# main.net
KiCad netlist of a schematic drawn in Altium Designer
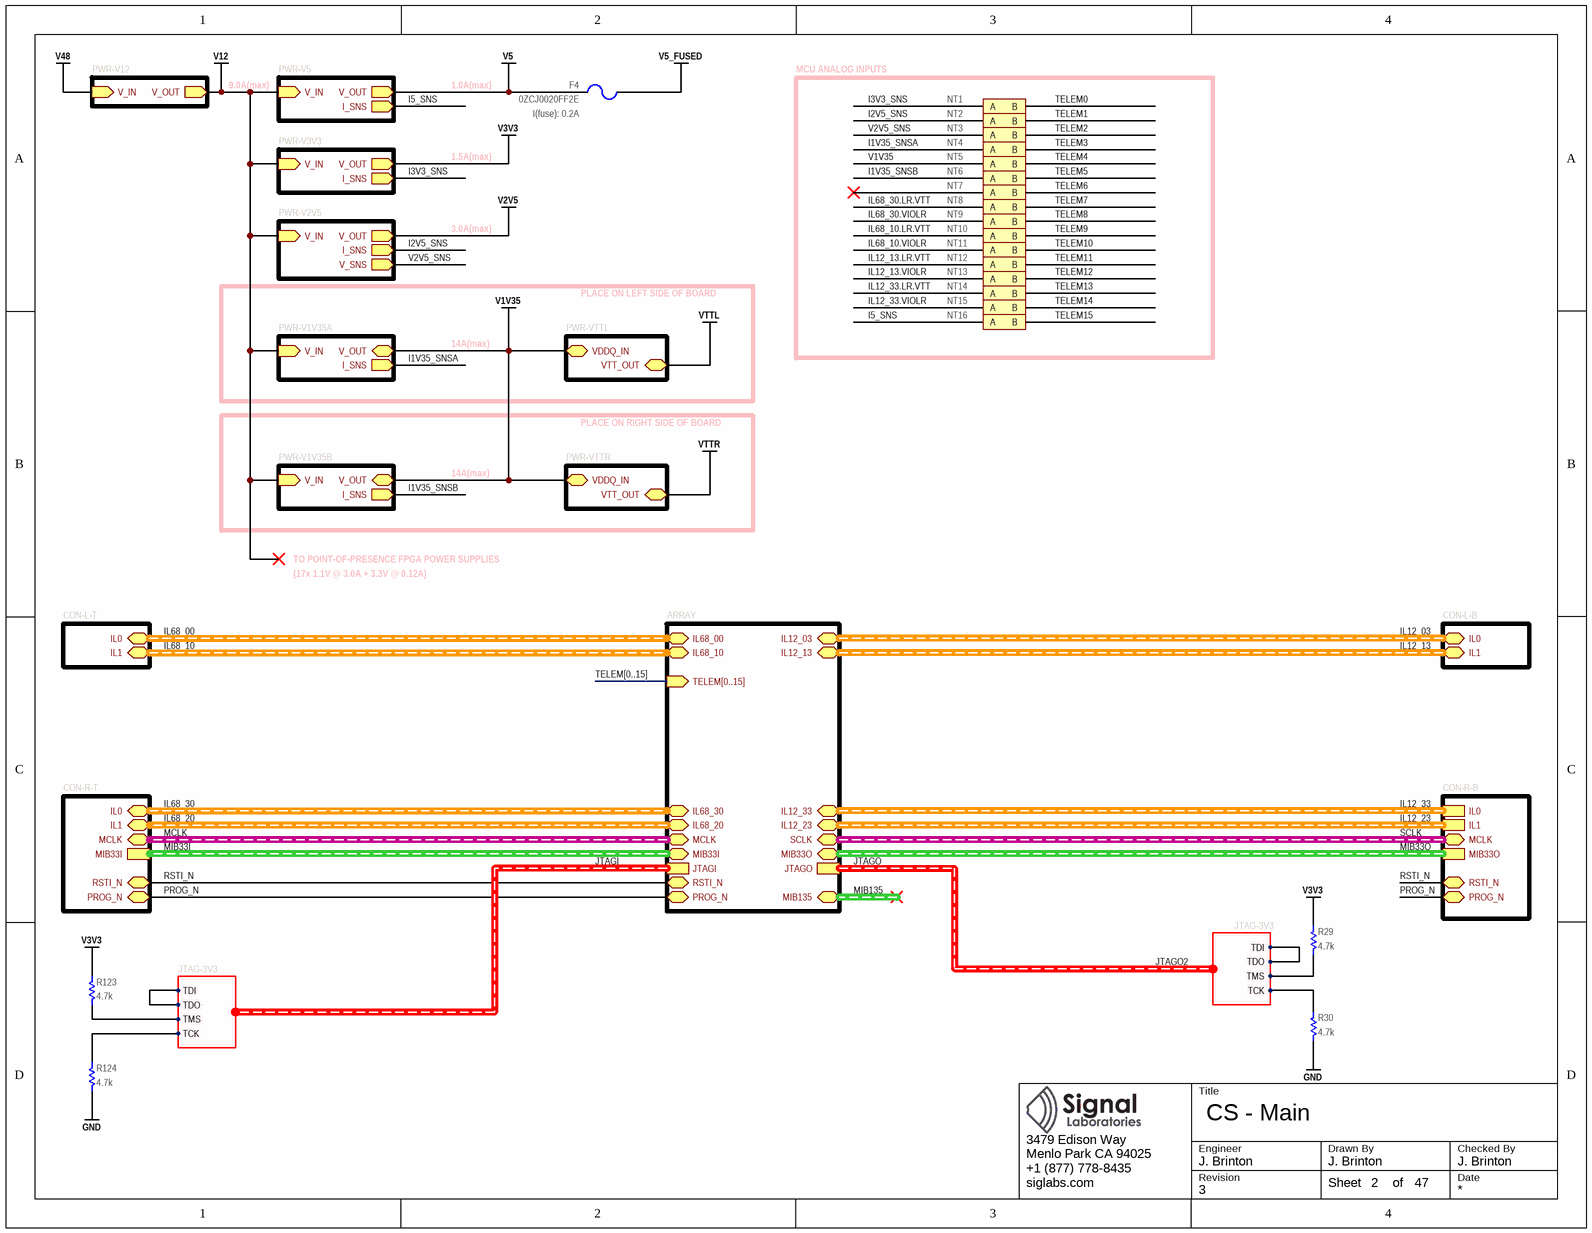
[diagram p0: main.SchDoc]

(export (version "E")
  (design (tool "Eeschema 10.0.6"))
  (components
    (comp (ref "F4")
      (value "0ZCJ0020FF2E")
      (footprint "generic:1206")
      (description "PTC Resettable Fuse, 0.2A, 30V, SMD 1206")
      (fields (field (name "MANUFACTURER") "Bell Fuse") (field (name "I(FUSE)") "0.2A"))
      (libsource (lib "bel-fuse") (part "0ZCJ0020FF2E"))
    )
    (comp (ref "NT1")
      (value "NET_TIE")
      (footprint "NET_TIE")
      (libsource (lib "copper_suicide") (part "NET_TIE"))
    )
    (comp (ref "NT2")
      (value "NET_TIE")
      (footprint "NET_TIE")
      (libsource (lib "copper_suicide") (part "NET_TIE"))
    )
    (comp (ref "NT3")
      (value "NET_TIE")
      (footprint "NET_TIE")
      (libsource (lib "copper_suicide") (part "NET_TIE"))
    )
    (comp (ref "NT4")
      (value "NET_TIE")
      (footprint "NET_TIE")
      (libsource (lib "copper_suicide") (part "NET_TIE"))
    )
    (comp (ref "NT5")
      (value "NET_TIE")
      (footprint "NET_TIE")
      (libsource (lib "copper_suicide") (part "NET_TIE"))
    )
    (comp (ref "NT6")
      (value "NET_TIE")
      (footprint "NET_TIE")
      (libsource (lib "copper_suicide") (part "NET_TIE"))
    )
    (comp (ref "NT7")
      (value "NET_TIE")
      (footprint "NET_TIE")
      (libsource (lib "copper_suicide") (part "NET_TIE"))
    )
    (comp (ref "NT8")
      (value "NET_TIE")
      (footprint "NET_TIE")
      (libsource (lib "copper_suicide") (part "NET_TIE"))
    )
    (comp (ref "NT9")
      (value "NET_TIE")
      (footprint "NET_TIE")
      (libsource (lib "copper_suicide") (part "NET_TIE"))
    )
    (comp (ref "NT10")
      (value "NET_TIE")
      (footprint "NET_TIE")
      (libsource (lib "copper_suicide") (part "NET_TIE"))
    )
    (comp (ref "NT11")
      (value "NET_TIE")
      (footprint "NET_TIE")
      (libsource (lib "copper_suicide") (part "NET_TIE"))
    )
    (comp (ref "NT12")
      (value "NET_TIE")
      (footprint "NET_TIE")
      (libsource (lib "copper_suicide") (part "NET_TIE"))
    )
    (comp (ref "NT13")
      (value "NET_TIE")
      (footprint "NET_TIE")
      (libsource (lib "copper_suicide") (part "NET_TIE"))
    )
    (comp (ref "NT14")
      (value "NET_TIE")
      (footprint "NET_TIE")
      (libsource (lib "copper_suicide") (part "NET_TIE"))
    )
    (comp (ref "NT15")
      (value "NET_TIE")
      (footprint "NET_TIE")
      (libsource (lib "copper_suicide") (part "NET_TIE"))
    )
    (comp (ref "NT16")
      (value "NET_TIE")
      (footprint "NET_TIE")
      (libsource (lib "copper_suicide") (part "NET_TIE"))
    )
    (comp (ref "R29")
      (value "4.7k")
      (footprint "RESC1005X40N")
      (description "Thick Film Resistor 4.7k ±1% 0.1W 75V 0402")
      (fields (field (name "TOLERANCE") "±1%") (field (name "MANUFACTURER") "Panasonic"))
      (libsource (lib "generic") (part "RES"))
    )
    (comp (ref "R30")
      (value "4.7k")
      (footprint "RESC1005X40N")
      (description "Thick Film Resistor 4.7k ±1% 0.1W 75V 0402")
      (fields (field (name "TOLERANCE") "±1%") (field (name "MANUFACTURER") "Panasonic"))
      (libsource (lib "generic") (part "RES"))
    )
    (comp (ref "R123")
      (value "4.7k")
      (footprint "RESC1005X40N")
      (description "Thick Film Resistor 4.7k ±1% 0.1W 75V 0402")
      (fields (field (name "TOLERANCE") "±1%") (field (name "MANUFACTURER") "Panasonic"))
      (libsource (lib "generic") (part "RES"))
    )
    (comp (ref "R124")
      (value "4.7k")
      (footprint "RESC1005X40N")
      (description "Thick Film Resistor 4.7k ±1% 0.1W 75V 0402")
      (fields (field (name "TOLERANCE") "±1%") (field (name "MANUFACTURER") "Panasonic"))
      (libsource (lib "generic") (part "RES"))
    )
  )
  (nets
    (net (code "16") (name "/I1V35_SNSA") (class "Default")
      (node (ref "NT4") (pin "A") (pinfunction "A_A") (pintype "passive"))
    )
    (net (code "17") (name "/I1V35_SNSB") (class "Default")
      (node (ref "NT6") (pin "A") (pinfunction "A_A") (pintype "passive"))
    )
    (net (code "18") (name "/I2V5_SNS") (class "Default")
      (node (ref "NT2") (pin "A") (pinfunction "A_A") (pintype "passive"))
    )
    (net (code "19") (name "/I3V3_SNS") (class "Default")
      (node (ref "NT1") (pin "A") (pinfunction "A_A") (pintype "passive"))
    )
    (net (code "20") (name "/I5_SNS") (class "Default")
      (node (ref "NT16") (pin "A") (pinfunction "A_A") (pintype "passive"))
    )
    (net (code "21") (name "/IL12_13.LR.VTT") (class "Default")
      (node (ref "NT12") (pin "A") (pinfunction "A_A") (pintype "passive"))
    )
    (net (code "22") (name "/IL12_13.VIOLR") (class "Default")
      (node (ref "NT13") (pin "A") (pinfunction "A_A") (pintype "passive"))
    )
    (net (code "23") (name "/IL12_33.LR.VTT") (class "Default")
      (node (ref "NT14") (pin "A") (pinfunction "A_A") (pintype "passive"))
    )
    (net (code "24") (name "/IL12_33.VIOLR") (class "Default")
      (node (ref "NT15") (pin "A") (pinfunction "A_A") (pintype "passive"))
    )
    (net (code "25") (name "/IL68_10.LR.VTT") (class "Default")
      (node (ref "NT10") (pin "A") (pinfunction "A_A") (pintype "passive"))
    )
    (net (code "26") (name "/IL68_10.VIOLR") (class "Default")
      (node (ref "NT11") (pin "A") (pinfunction "A_A") (pintype "passive"))
    )
    (net (code "27") (name "/IL68_30.LR.VTT") (class "Default")
      (node (ref "NT8") (pin "A") (pinfunction "A_A") (pintype "passive"))
    )
    (net (code "28") (name "/IL68_30.VIOLR") (class "Default")
      (node (ref "NT9") (pin "A") (pinfunction "A_A") (pintype "passive"))
    )
    (net (code "33") (name "/TELEM0") (class "Default")
      (node (ref "NT1") (pin "B") (pinfunction "B_B") (pintype "passive"))
    )
    (net (code "34") (name "/TELEM1") (class "Default")
      (node (ref "NT2") (pin "B") (pinfunction "B_B") (pintype "passive"))
    )
    (net (code "35") (name "/TELEM2") (class "Default")
      (node (ref "NT3") (pin "B") (pinfunction "B_B") (pintype "passive"))
    )
    (net (code "36") (name "/TELEM3") (class "Default")
      (node (ref "NT4") (pin "B") (pinfunction "B_B") (pintype "passive"))
    )
    (net (code "37") (name "/TELEM4") (class "Default")
      (node (ref "NT5") (pin "B") (pinfunction "B_B") (pintype "passive"))
    )
    (net (code "38") (name "/TELEM5") (class "Default")
      (node (ref "NT6") (pin "B") (pinfunction "B_B") (pintype "passive"))
    )
    (net (code "39") (name "/TELEM6") (class "Default")
      (node (ref "NT7") (pin "B") (pinfunction "B_B") (pintype "passive"))
    )
    (net (code "40") (name "/TELEM7") (class "Default")
      (node (ref "NT8") (pin "B") (pinfunction "B_B") (pintype "passive"))
    )
    (net (code "41") (name "/TELEM8") (class "Default")
      (node (ref "NT9") (pin "B") (pinfunction "B_B") (pintype "passive"))
    )
    (net (code "42") (name "/TELEM9") (class "Default")
      (node (ref "NT10") (pin "B") (pinfunction "B_B") (pintype "passive"))
    )
    (net (code "43") (name "/TELEM10") (class "Default")
      (node (ref "NT11") (pin "B") (pinfunction "B_B") (pintype "passive"))
    )
    (net (code "44") (name "/TELEM11") (class "Default")
      (node (ref "NT12") (pin "B") (pinfunction "B_B") (pintype "passive"))
    )
    (net (code "45") (name "/TELEM12") (class "Default")
      (node (ref "NT13") (pin "B") (pinfunction "B_B") (pintype "passive"))
    )
    (net (code "46") (name "/TELEM13") (class "Default")
      (node (ref "NT14") (pin "B") (pinfunction "B_B") (pintype "passive"))
    )
    (net (code "47") (name "/TELEM14") (class "Default")
      (node (ref "NT15") (pin "B") (pinfunction "B_B") (pintype "passive"))
    )
    (net (code "48") (name "/TELEM15") (class "Default")
      (node (ref "NT16") (pin "B") (pinfunction "B_B") (pintype "passive"))
    )
    (net (code "50") (name "/V2V5_SNS") (class "Default")
      (node (ref "NT3") (pin "A") (pinfunction "A_A") (pintype "passive"))
    )
    (net (code "64") (name "GND") (class "Default")
      (node (ref "R124") (pin "1") (pinfunction "1_1") (pintype "passive"))
      (node (ref "R30") (pin "1") (pinfunction "1_1") (pintype "passive"))
    )
    (net (code "65") (name "V1V35") (class "Default")
      (node (ref "NT5") (pin "A") (pinfunction "A_A") (pintype "passive"))
    )
    (net (code "67") (name "V3V3") (class "Default")
      (node (ref "R123") (pin "2") (pinfunction "2_2") (pintype "passive"))
      (node (ref "R29") (pin "2") (pinfunction "2_2") (pintype "passive"))
    )
    (net (code "68") (name "V5") (class "Default")
      (node (ref "F4") (pin "1") (pinfunction "1_1") (pintype "passive"))
    )
    (net (code "69") (name "V5_FUSED") (class "Default")
      (node (ref "F4") (pin "2") (pinfunction "2_2") (pintype "passive"))
    )
    (net (code "74") (name "unconnected-(NT7-PadA)") (class "Default")
      (node (ref "NT7") (pin "A") (pinfunction "A_A") (pintype "passive+no_connect"))
    )
    (net (code "75") (name "unconnected-(R29-Pad1)") (class "Default")
      (node (ref "R29") (pin "1") (pinfunction "1_1") (pintype "passive"))
    )
    (net (code "76") (name "unconnected-(R30-Pad2)") (class "Default")
      (node (ref "R30") (pin "2") (pinfunction "2_2") (pintype "passive"))
    )
    (net (code "77") (name "unconnected-(R123-Pad1)") (class "Default")
      (node (ref "R123") (pin "1") (pinfunction "1_1") (pintype "passive"))
    )
    (net (code "78") (name "unconnected-(R124-Pad2)") (class "Default")
      (node (ref "R124") (pin "2") (pinfunction "2_2") (pintype "passive"))
    )
  )
)
